# Sheet1.net
KiCad netlist of a schematic drawn in Altium Designer
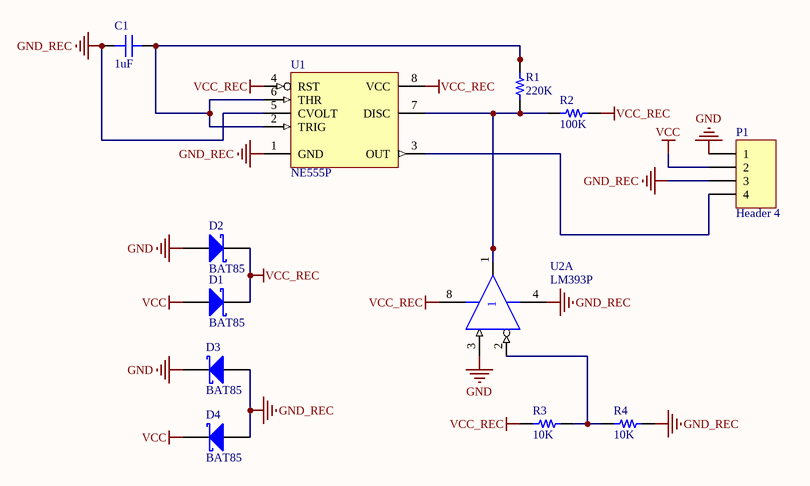
[diagram p0: Sheet1.SchDoc]

(export (version "E")
  (design (tool "Eeschema 10.0.6"))
  (components
    (comp (ref "C1")
      (value "1uF")
      (footprint "CAP 0805/2012")
      (description "CAP CER 10000PF 50V X7R 0805")
      (fields (field (name "PART NUMBER") "CC0805KRX7R9BB103") (field (name "MANUFACTURER") "Yageo"))
      (libsource (lib "Database_Libs1") (part "Capacitor"))
    )
    (comp (ref "D1")
      (value "BAT85")
      (footprint "SOD68")
      (description "Schottky Barrier Diode")
      (fields (field (name "PUBLISHER") "Altium Limited"))
      (libsource (lib "Philips Discrete Diode - Schottky") (part "BAT85"))
    )
    (comp (ref "D2")
      (value "BAT85")
      (footprint "SOD68")
      (description "Schottky Barrier Diode")
      (fields (field (name "PUBLISHER") "Altium Limited"))
      (libsource (lib "Philips Discrete Diode - Schottky") (part "BAT85"))
    )
    (comp (ref "D3")
      (value "BAT85")
      (footprint "SOD68")
      (description "Schottky Barrier Diode")
      (fields (field (name "PUBLISHER") "Altium Limited"))
      (libsource (lib "Philips Discrete Diode - Schottky") (part "BAT85"))
    )
    (comp (ref "D4")
      (value "BAT85")
      (footprint "SOD68")
      (description "Schottky Barrier Diode")
      (fields (field (name "PUBLISHER") "Altium Limited"))
      (libsource (lib "Philips Discrete Diode - Schottky") (part "BAT85"))
    )
    (comp (ref "P1")
      (value "Header 4")
      (footprint "HDR1X4")
      (description "Header, 4-Pin")
      (fields (field (name "PUBLISHER") "Altium Limited"))
      (libsource (lib "Miscellaneous Connectors") (part "Header 4"))
    )
    (comp (ref "R1")
      (value "220K")
      (footprint "RES 0805/2012")
      (description "RES SMD 49.9 OHM 1% 1/8W 0805")
      (fields
        (field (name "PART NUMBER") "ERJ-6ENF49R9V")
        (field (name "MANUFACTURER") "Panasonic Electronic Components")
      )
      (libsource (lib "Database_Libs1") (part "Resistor"))
    )
    (comp (ref "R2")
      (value "100K")
      (footprint "RES 0805/2012")
      (description "RES SMD 49.9 OHM 1% 1/8W 0805")
      (fields
        (field (name "PART NUMBER") "ERJ-6ENF49R9V")
        (field (name "MANUFACTURER") "Panasonic Electronic Components")
      )
      (libsource (lib "Database_Libs1") (part "Resistor"))
    )
    (comp (ref "R3")
      (value "10K")
      (footprint "RES 0805/2012")
      (description "RES SMD 49.9 OHM 1% 1/8W 0805")
      (fields
        (field (name "PART NUMBER") "ERJ-6ENF49R9V")
        (field (name "MANUFACTURER") "Panasonic Electronic Components")
      )
      (libsource (lib "Database_Libs1") (part "Resistor"))
    )
    (comp (ref "R4")
      (value "10K")
      (footprint "RES 0805/2012")
      (description "RES SMD 49.9 OHM 1% 1/8W 0805")
      (fields
        (field (name "PART NUMBER") "ERJ-6ENF49R9V")
        (field (name "MANUFACTURER") "Panasonic Electronic Components")
      )
      (libsource (lib "Database_Libs1") (part "Resistor"))
    )
    (comp (ref "U1")
      (value "NE555P")
      (footprint "P008")
      (description "Precision Timer")
      (fields (field (name "PUBLISHER") "Altium Limited"))
      (libsource (lib "TI Analog Timer Circuit") (part "NE555P"))
    )
    (comp (ref "U2")
      (value "LM393P")
      (footprint "P008")
      (description "Dual Differential Comparator")
      (fields (field (name "PUBLISHER") "Altium Limited"))
      (libsource (lib "TI Logic Comparator") (part "LM393P"))
    )
  )
  (nets
    (net (code "1") (name "GND") (class "Default")
      (node (ref "D2") (pin "1") (pinfunction "A_1") (pintype "passive"))
      (node (ref "D3") (pin "2") (pinfunction "K_2") (pintype "passive"))
      (node (ref "P1") (pin "1") (pinfunction "1_1") (pintype "passive"))
      (node (ref "U2") (pin "3") (pinfunction "IN+_3") (pintype "input"))
    )
    (net (code "2") (name "GND_REC") (class "Default")
      (node (ref "C1") (pin "1") (pinfunction "1_1") (pintype "passive"))
      (node (ref "D3") (pin "1") (pinfunction "A_1") (pintype "passive"))
      (node (ref "D4") (pin "1") (pinfunction "A_1") (pintype "passive"))
      (node (ref "P1") (pin "3") (pinfunction "3_3") (pintype "passive"))
      (node (ref "R4") (pin "1") (pinfunction "1_1") (pintype "passive"))
      (node (ref "U1") (pin "1") (pinfunction "GND_1") (pintype "power_in"))
      (node (ref "U1") (pin "5") (pinfunction "CVOLT_5") (pintype "passive"))
      (node (ref "U2") (pin "4") (pinfunction "GND_4") (pintype "power_in"))
    )
    (net (code "3") (name "Net-(U1-DISC)") (class "Default")
      (node (ref "R1") (pin "1") (pinfunction "1_1") (pintype "passive"))
      (node (ref "R2") (pin "2") (pinfunction "2_2") (pintype "passive"))
      (node (ref "U1") (pin "7") (pinfunction "DISC_7") (pintype "open_collector"))
      (node (ref "U2") (pin "1") (pinfunction "OUT_1") (pintype "open_collector"))
    )
    (net (code "4") (name "Net-(U1-OUT)") (class "Default")
      (node (ref "P1") (pin "4") (pinfunction "4_4") (pintype "passive"))
      (node (ref "U1") (pin "3") (pinfunction "OUT_3") (pintype "output"))
    )
    (net (code "5") (name "Net-(U1-THR)") (class "Default")
      (node (ref "C1") (pin "2") (pinfunction "2_2") (pintype "passive"))
      (node (ref "R1") (pin "2") (pinfunction "2_2") (pintype "passive"))
      (node (ref "U1") (pin "2") (pinfunction "TRIG_2") (pintype "input"))
      (node (ref "U1") (pin "6") (pinfunction "THR_6") (pintype "input"))
    )
    (net (code "6") (name "Net-(U2A-IN-)") (class "Default")
      (node (ref "R3") (pin "1") (pinfunction "1_1") (pintype "passive"))
      (node (ref "R4") (pin "2") (pinfunction "2_2") (pintype "passive"))
      (node (ref "U2") (pin "2") (pinfunction "IN-_2") (pintype "input"))
    )
    (net (code "7") (name "VCC") (class "Default")
      (node (ref "D1") (pin "1") (pinfunction "A_1") (pintype "passive"))
      (node (ref "D4") (pin "2") (pinfunction "K_2") (pintype "passive"))
      (node (ref "P1") (pin "2") (pinfunction "2_2") (pintype "passive"))
    )
    (net (code "8") (name "VCC_REC") (class "Default")
      (node (ref "D1") (pin "2") (pinfunction "K_2") (pintype "passive"))
      (node (ref "D2") (pin "2") (pinfunction "K_2") (pintype "passive"))
      (node (ref "R2") (pin "1") (pinfunction "1_1") (pintype "passive"))
      (node (ref "R3") (pin "2") (pinfunction "2_2") (pintype "passive"))
      (node (ref "U1") (pin "4") (pinfunction "RST_4") (pintype "input"))
      (node (ref "U1") (pin "8") (pinfunction "VCC_8") (pintype "power_in"))
      (node (ref "U2") (pin "8") (pinfunction "VCC_8") (pintype "power_in"))
    )
  )
)
